# LacewingPXE_v3p1.net
KiCad netlist of a schematic drawn in Altium Designer
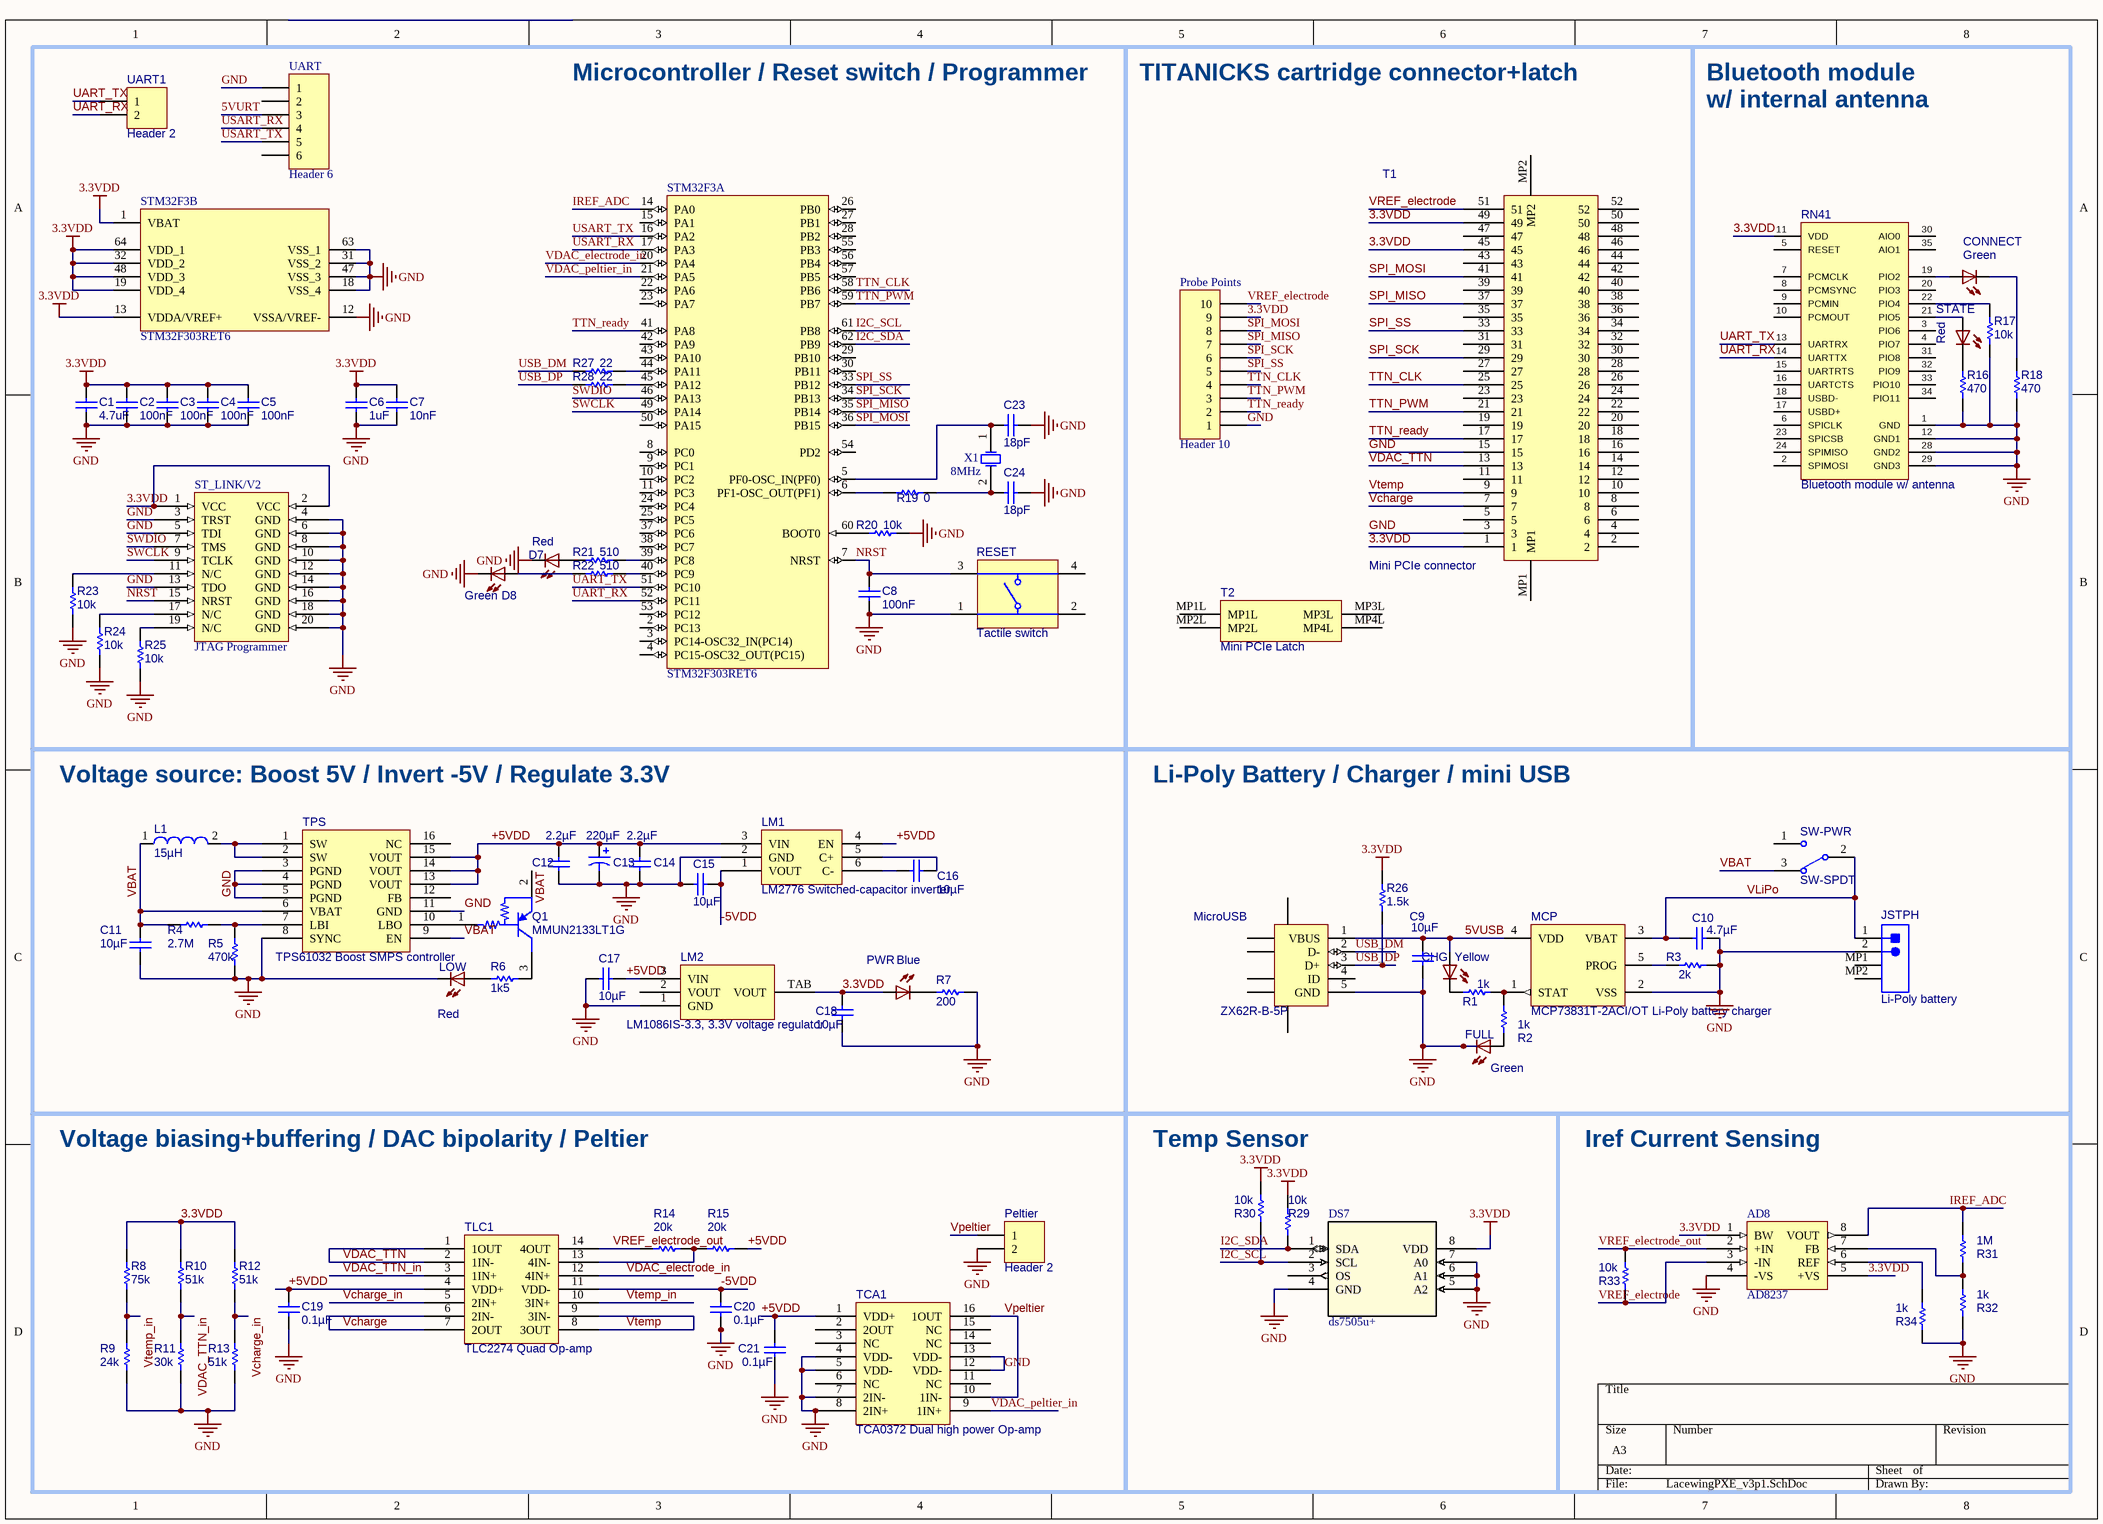
[diagram p0: LacewingPXE_v3p1.SchDoc]

(export (version "E")
  (design (tool "Eeschema 10.0.6"))
  (components
    (comp (ref "AD8")
      (value "AD8237")
      (footprint "ADI-RM-8_N")
      (libsource (lib "Device_mbd_v1") (part "AD8237"))
    )
    (comp (ref "C1")
      (value "4.7uF")
      (footprint "CAPC0603(1608)100_N")
      (description "Ceramic CAP0603 (1608 Metric) Thickness 1mm SMD")
      (libsource (lib "Altium Content Vault") (part "CAP"))
    )
    (comp (ref "C2")
      (value "100nF")
      (footprint "CAPC0603(1608)100_N")
      (description "Ceramic CAP0603 (1608 Metric) Thickness 1mm SMD")
      (libsource (lib "Altium Content Vault") (part "CAP"))
    )
    (comp (ref "C3")
      (value "100nF")
      (footprint "CAPC0603(1608)100_N")
      (description "Ceramic CAP0603 (1608 Metric) Thickness 1mm SMD")
      (libsource (lib "Altium Content Vault") (part "CAP"))
    )
    (comp (ref "C4")
      (value "100nF")
      (footprint "CAPC0603(1608)100_N")
      (description "Ceramic CAP0603 (1608 Metric) Thickness 1mm SMD")
      (libsource (lib "Altium Content Vault") (part "CAP"))
    )
    (comp (ref "C5")
      (value "100nF")
      (footprint "CAPC0603(1608)100_N")
      (description "Ceramic CAP0603 (1608 Metric) Thickness 1mm SMD")
      (libsource (lib "Altium Content Vault") (part "CAP"))
    )
    (comp (ref "C6")
      (value "1uF")
      (footprint "CAPC0603(1608)100_N")
      (description "Ceramic CAP0603 (1608 Metric) Thickness 1mm SMD")
      (libsource (lib "Altium Content Vault") (part "CAP"))
    )
    (comp (ref "C7")
      (value "10nF")
      (footprint "CAPC0603(1608)100_N")
      (description "Ceramic CAP0603 (1608 Metric) Thickness 1mm SMD")
      (libsource (lib "Altium Content Vault") (part "CAP"))
    )
    (comp (ref "C8")
      (value "100nF")
      (footprint "CAPC0603(1608)100_N")
      (description "Ceramic CAP0603 (1608 Metric) Thickness 1mm SMD")
      (libsource (lib "Altium Content Vault") (part "CAP"))
    )
    (comp (ref "C9")
      (value "10µF")
      (footprint "CAPC0805(2012)75_N")
      (description "Ceramic CAP0805 (2012 Metric) Thickness 0.75mm SMD")
      (libsource (lib "Altium Content Vault") (part "CMP-1036-00002-1"))
    )
    (comp (ref "C10")
      (value "4.7µF")
      (footprint "CAPC0603(1608)100_N")
      (description "Ceramic CAP0603 (1608 Metric) Thickness 1mm SMD")
      (libsource (lib "Altium Content Vault") (part "CAP"))
    )
    (comp (ref "C11")
      (value "10µF")
      (footprint "CAPC0805(2012)75_N")
      (description "Ceramic CAP0805 (2012 Metric) Thickness 0.75mm SMD")
      (libsource (lib "Altium Content Vault") (part "CMP-1036-00002-1"))
    )
    (comp (ref "C12")
      (value "2.2µF")
      (footprint "CAPC0805(2012)75_N")
      (description "Ceramic CAP0805 (2012 Metric) Thickness 0.75mm SMD")
      (libsource (lib "Altium Content Vault") (part "CMP-1036-00002-1"))
    )
    (comp (ref "C13")
      (value "220µF")
      (footprint "AVX-CAPC7343_V")
      (description "Capacitor, Tantalum, 220uF 10% 10V MCCT-D (7343-31)")
      (fields (field (name "PARTNUMBER") "TAJD227K010R") (field (name "MANUFACTURER") "AVX"))
      (libsource (lib "Altium Content Vault") (part "CMP-0279-00002-1"))
    )
    (comp (ref "C14")
      (value "2.2µF")
      (footprint "CAPC0805(2012)75_N")
      (description "Ceramic CAP0805 (2012 Metric) Thickness 0.75mm SMD")
      (libsource (lib "Altium Content Vault") (part "CMP-1036-00002-1"))
    )
    (comp (ref "C15")
      (value "10µF")
      (footprint "CAPC0805(2012)75_N")
      (description "Ceramic CAP0805 (2012 Metric) Thickness 0.75mm SMD")
      (libsource (lib "Altium Content Vault") (part "CMP-1036-00002-1"))
    )
    (comp (ref "C16")
      (value "10µF")
      (footprint "CAPC0805(2012)75_N")
      (description "Ceramic CAP0805 (2012 Metric) Thickness 0.75mm SMD")
      (libsource (lib "Altium Content Vault") (part "CMP-1036-00002-1"))
    )
    (comp (ref "C17")
      (value "10µF")
      (footprint "CAPC0805(2012)75_N")
      (description "Ceramic CAP0805 (2012 Metric) Thickness 0.75mm SMD")
      (libsource (lib "Altium Content Vault") (part "CMP-1036-00002-1"))
    )
    (comp (ref "C18")
      (value "10µF")
      (footprint "CAPC0805(2012)75_N")
      (description "Ceramic CAP0805 (2012 Metric) Thickness 0.75mm SMD")
      (libsource (lib "Altium Content Vault") (part "CMP-1036-00002-1"))
    )
    (comp (ref "C19")
      (value "0.1µF")
      (footprint "CAPC0603(1608)100_N")
      (description "Ceramic CAP0603 (1608 Metric) Thickness 1mm SMD")
      (libsource (lib "Device_mbd_v1") (part "CAP"))
    )
    (comp (ref "C20")
      (value "0.1µF")
      (footprint "CAPC0603(1608)100_N")
      (description "Ceramic CAP0603 (1608 Metric) Thickness 1mm SMD")
      (libsource (lib "Device_mbd_v1") (part "CAP"))
    )
    (comp (ref "C21")
      (value "0.1µF")
      (footprint "CAPC0603(1608)100_N")
      (description "Ceramic CAP0603 (1608 Metric) Thickness 1mm SMD")
      (libsource (lib "Device_mbd_v1") (part "CAP"))
    )
    (comp (ref "C23")
      (value "18pF")
      (footprint "CAPC0603(1608)100_N")
      (description "Ceramic CAP0603 (1608 Metric) Thickness 1mm SMD")
      (libsource (lib "Altium Content Vault") (part "CAP"))
    )
    (comp (ref "C24")
      (value "18pF")
      (footprint "CAPC0603(1608)100_N")
      (description "Ceramic CAP0603 (1608 Metric) Thickness 1mm SMD")
      (libsource (lib "Altium Content Vault") (part "CAP"))
    )
    (comp (ref "CHG")
      (value "Yellow")
      (footprint "LED-0603")
      (description "LED SMD 0603")
      (libsource (lib "TTN_chip") (part "LED0603"))
    )
    (comp (ref "CONNECT")
      (value "Green")
      (footprint "LED-0603")
      (description "LED SMD 0603")
      (libsource (lib "TTN_chip") (part "LED0603"))
    )
    (comp (ref "D7")
      (value "Red")
      (footprint "LED-0603")
      (description "LED SMD 0603")
      (libsource (lib "TTN_chip") (part "LED0603"))
    )
    (comp (ref "D8")
      (value "Green")
      (footprint "LED-0603")
      (description "LED SMD 0603")
      (libsource (lib "TTN_chip") (part "LED0603"))
    )
    (comp (ref "DS7")
      (value "ds7505u+")
      (footprint "21-0036K")
      (description "No Description Available")
      (fields (field (name "COPYRIGHT") "Copyright (C) 2018 Accelerated Designs. All rights reserved"))
      (libsource (lib "2019-05-15_15-51-07") (part "ds7505u+"))
    )
    (comp (ref "FULL")
      (value "Green")
      (footprint "LED-0603")
      (description "LED SMD 0603")
      (libsource (lib "TTN_chip") (part "LED0603"))
    )
    (comp (ref "JSTPH")
      (value "Li-Poly battery")
      (footprint "JST- S2B-PH-SM4-TB(LF)(SN)-2_V")
      (description "JST PH 2-pin 2-holder SMD")
      (libsource (lib "Altium Content Vault") (part "SYM-0368-00001-1"))
    )
    (comp (ref "L1")
      (value "15µH")
      (footprint "WE-PD 1050")
      (description "SMD-Shielded Power Inductor WE-PD 7447714150, L=15 µH")
      (libsource (lib "Altium Content Vault") (part "PAS-IND-INDUCTOR-2"))
    )
    (comp (ref "LM1")
      (value "LM2776 Switched-capacitor inverter")
      (footprint "TI-DBV6_M")
      (libsource (lib "Device_mbd_v1") (part "LM2776"))
    )
    (comp (ref "LM2")
      (value "LM1086IS-3.3, 3.3V voltage regulator")
      (footprint "TS3B_M")
      (libsource (lib "TTN_chip") (part "LM1086IS-3.3"))
    )
    (comp (ref "LOW")
      (value "Red")
      (footprint "LED-0603")
      (description "LED SMD 0603")
      (libsource (lib "TTN_chip") (part "LED0603"))
    )
    (comp (ref "MCP")
      (value "MCP73831T-2ACI/OT Li-Poly battery charger")
      (footprint "SOT-23-OT5_M")
      (libsource (lib "Altium Content Vault") (part "CMP-0133-00143-1"))
    )
    (comp (ref "MicroUSB")
      (value "ZX62R-B-5P")
      (footprint "HIRO-ZX62R-B-5P_V")
      (description "Connector; USBMicro-B,Reverse type, SMT; 5 Position; Right Angle")
      (libsource (lib "Altium Content Vault") (part "HIRO-ZX62R-B-5P-5"))
    )
    (comp (ref "Peltier")
      (value "Header 2")
      (footprint "HDR1X2")
      (description "Header, 2-Pin")
      (fields (field (name "PUBLISHER") "Altium Limited"))
      (libsource (lib "Miscellaneous Connectors") (part "Header 2"))
    )
    (comp (ref "Probe Points")
      (value "Header 10")
      (footprint "HDR1X10")
      (description "Header, 10-Pin")
      (fields (field (name "PUBLISHER") "Altium Limited"))
      (libsource (lib "Miscellaneous Connectors") (part "Header 10"))
    )
    (comp (ref "PWR")
      (value "Blue")
      (footprint "LED-0603")
      (description "LED SMD 0603")
      (libsource (lib "TTN_chip") (part "LED0603"))
    )
    (comp (ref "Q1")
      (value "MMUN2133LT1G")
      (footprint "ONSC-SOT-23-3-318-08_V")
      (libsource (lib "Altium Content Vault") (part "CMP-0630-00284-1"))
    )
    (comp (ref "R1")
      (value "1k")
      (footprint "RESC0603(1608)_N")
      (description "RES0603 (1608 Metric)  SMD")
      (libsource (lib "Altium Content Vault") (part "RES"))
    )
    (comp (ref "R2")
      (value "1k")
      (footprint "RESC0603(1608)_N")
      (description "RES0603 (1608 Metric)  SMD")
      (libsource (lib "Altium Content Vault") (part "RES"))
    )
    (comp (ref "R3")
      (value "2k")
      (footprint "RESC0603(1608)_N")
      (description "RES0603 (1608 Metric)  SMD")
      (libsource (lib "Altium Content Vault") (part "RES"))
    )
    (comp (ref "R4")
      (value "2.7M")
      (footprint "RESC0603(1608)_N")
      (description "RES0603 (1608 Metric)  SMD")
      (libsource (lib "Altium Content Vault") (part "RES"))
    )
    (comp (ref "R5")
      (value "470k")
      (footprint "RESC0603(1608)_N")
      (description "RES0603 (1608 Metric)  SMD")
      (libsource (lib "Altium Content Vault") (part "RES"))
    )
    (comp (ref "R6")
      (value "1k5")
      (footprint "RESC0603(1608)_N")
      (description "RES0603 (1608 Metric)  SMD")
      (libsource (lib "Altium Content Vault") (part "RES"))
    )
    (comp (ref "R7")
      (value "200")
      (footprint "RESC0603(1608)_N")
      (description "RES0603 (1608 Metric)  SMD")
      (libsource (lib "Altium Content Vault") (part "RES"))
    )
    (comp (ref "R8")
      (value "75k")
      (footprint "RESC0603(1608)_N")
      (description "RES0603 (1608 Metric)  SMD")
      (libsource (lib "Altium Content Vault") (part "RES"))
    )
    (comp (ref "R9")
      (value "24k")
      (footprint "RESC0603(1608)_N")
      (description "RES0603 (1608 Metric)  SMD")
      (libsource (lib "Altium Content Vault") (part "RES"))
    )
    (comp (ref "R10")
      (value "51k")
      (footprint "RESC0603(1608)_N")
      (description "RES0603 (1608 Metric)  SMD")
      (libsource (lib "Altium Content Vault") (part "RES"))
    )
    (comp (ref "R11")
      (value "30k")
      (footprint "RESC0603(1608)_N")
      (description "RES0603 (1608 Metric)  SMD")
      (libsource (lib "Altium Content Vault") (part "RES"))
    )
    (comp (ref "R12")
      (value "51k")
      (footprint "RESC0603(1608)_N")
      (description "RES0603 (1608 Metric)  SMD")
      (libsource (lib "Altium Content Vault") (part "RES"))
    )
    (comp (ref "R13")
      (value "51k")
      (footprint "RESC0603(1608)_N")
      (description "RES0603 (1608 Metric)  SMD")
      (libsource (lib "Altium Content Vault") (part "RES"))
    )
    (comp (ref "R14")
      (value "20k")
      (footprint "RESC0603(1608)_N")
      (description "RES0603 (1608 Metric)  SMD")
      (libsource (lib "Altium Content Vault") (part "RES"))
    )
    (comp (ref "R15")
      (value "20k")
      (footprint "RESC0603(1608)_N")
      (description "RES0603 (1608 Metric)  SMD")
      (libsource (lib "Altium Content Vault") (part "RES"))
    )
    (comp (ref "R16")
      (value "470")
      (footprint "RESC0603(1608)_N")
      (description "RES0603 (1608 Metric)  SMD")
      (libsource (lib "Altium Content Vault") (part "RES"))
    )
    (comp (ref "R17")
      (value "10k")
      (footprint "RESC0603(1608)_N")
      (description "RES0603 (1608 Metric)  SMD")
      (libsource (lib "Altium Content Vault") (part "RES"))
    )
    (comp (ref "R18")
      (value "470")
      (footprint "RESC0603(1608)_N")
      (description "RES0603 (1608 Metric)  SMD")
      (libsource (lib "Altium Content Vault") (part "RES"))
    )
    (comp (ref "R19")
      (value "0")
      (footprint "RESC0603(1608)_N")
      (description "RES0603 (1608 Metric)  SMD")
      (libsource (lib "Altium Content Vault") (part "RES"))
    )
    (comp (ref "R20")
      (value "10k")
      (footprint "RESC0603(1608)_N")
      (description "RES0603 (1608 Metric)  SMD")
      (libsource (lib "Altium Content Vault") (part "RES"))
    )
    (comp (ref "R21")
      (value "510")
      (footprint "RESC0603(1608)_N")
      (description "RES0603 (1608 Metric)  SMD")
      (libsource (lib "Altium Content Vault") (part "RES"))
    )
    (comp (ref "R22")
      (value "510")
      (footprint "RESC0603(1608)_N")
      (description "RES0603 (1608 Metric)  SMD")
      (libsource (lib "Altium Content Vault") (part "RES"))
    )
    (comp (ref "R23")
      (value "10k")
      (footprint "RESC0603(1608)_N")
      (description "RES0603 (1608 Metric)  SMD")
      (libsource (lib "Altium Content Vault") (part "RES"))
    )
    (comp (ref "R24")
      (value "10k")
      (footprint "RESC0603(1608)_N")
      (description "RES0603 (1608 Metric)  SMD")
      (libsource (lib "Altium Content Vault") (part "RES"))
    )
    (comp (ref "R25")
      (value "10k")
      (footprint "RESC0603(1608)_N")
      (description "RES0603 (1608 Metric)  SMD")
      (libsource (lib "Altium Content Vault") (part "RES"))
    )
    (comp (ref "R26")
      (value "1.5k")
      (footprint "RESC0603(1608)_N")
      (description "RES0603 (1608 Metric)  SMD")
      (libsource (lib "Altium Content Vault") (part "RES"))
    )
    (comp (ref "R27")
      (value "22")
      (footprint "RESC0603(1608)_N")
      (description "RES0603 (1608 Metric)  SMD")
      (libsource (lib "Altium Content Vault") (part "RES"))
    )
    (comp (ref "R28")
      (value "22")
      (footprint "RESC0603(1608)_N")
      (description "RES0603 (1608 Metric)  SMD")
      (libsource (lib "Altium Content Vault") (part "RES"))
    )
    (comp (ref "R29")
      (value "10k")
      (footprint "RESC0603(1608)_N")
      (description "RES0603 (1608 Metric)  SMD")
      (libsource (lib "Altium Content Vault") (part "RES"))
    )
    (comp (ref "R30")
      (value "10k")
      (footprint "RESC0603(1608)_N")
      (description "RES0603 (1608 Metric)  SMD")
      (libsource (lib "Altium Content Vault") (part "RES"))
    )
    (comp (ref "R31")
      (value "1M")
      (footprint "RESC0603(1608)_N")
      (description "RES0603 (1608 Metric)  SMD")
      (libsource (lib "Altium Content Vault") (part "RES"))
    )
    (comp (ref "R32")
      (value "1k")
      (footprint "RESC0603(1608)_N")
      (description "RES0603 (1608 Metric)  SMD")
      (libsource (lib "Altium Content Vault") (part "RES"))
    )
    (comp (ref "R33")
      (value "10k")
      (footprint "RESC0603(1608)_N")
      (description "RES0603 (1608 Metric)  SMD")
      (libsource (lib "Altium Content Vault") (part "RES"))
    )
    (comp (ref "R34")
      (value "1k")
      (footprint "RESC0603(1608)_N")
      (description "RES0603 (1608 Metric)  SMD")
      (libsource (lib "Altium Content Vault") (part "RES"))
    )
    (comp (ref "RESET")
      (value "Tactile switch")
      (footprint "OMRON-B3F-1000-4_V")
      (description "ORMON B3F-10XX")
      (libsource (lib "TTN_chip") (part "SW-SPST-4_A"))
    )
    (comp (ref "RN41")
      (value "Bluetooth module w/ antenna")
      (footprint "RN41")
      (description "Bluetooth SMD module")
      (libsource (lib "Device_mbd_v1") (part "BLUETOOTH-RN41"))
    )
    (comp (ref "STATE")
      (value "Red")
      (footprint "LED-0603")
      (description "LED SMD 0603")
      (libsource (lib "TTN_chip") (part "LED0603"))
    )
    (comp (ref "STM32F3")
      (value "STM32F303RET6")
      (footprint "STM-LQFP64_V")
      (fields (field (name "PARTNUMBER") "STM32F303RBT6"))
      (libsource (lib "STMicroelectronics STM32 F3 new") (part "STM32F303RBT6_1"))
    )
    (comp (ref "ST_LINK/V2")
      (value "JTAG Programmer")
      (footprint "JTAG2")
      (libsource (lib "Device_mbd_v1") (part "JTAG"))
    )
    (comp (ref "SW-PWR")
      (value "SW-SPDT")
      (footprint "SWITCH SPDT CS12ANW03")
      (description "Switch SPDT CS12ANW03")
      (libsource (lib "TTN_chip") (part "SW-SPDT"))
    )
    (comp (ref "T1")
      (value "Mini PCIe connector")
      (footprint "Molex Conn-67910")
      (libsource (lib "Device_mbd_v1") (part "Mini PCIe connector"))
    )
    (comp (ref "T2")
      (value "Mini PCIe Latch")
      (footprint "Molex Latch-48099")
      (libsource (lib "Device_mbd_v1") (part "Mini PCIe Latch"))
    )
    (comp (ref "TCA1")
      (value "TCA0372 Dual high power Op-amp")
      (footprint "ONSC-SOIC-16-751G-03_V")
      (libsource (lib "TTN_chip") (part "TCA0372"))
    )
    (comp (ref "TLC1")
      (value "TLC2274 Quad Op-amp")
      (footprint "TI-D14_M")
      (libsource (lib "TTN_chip") (part "TLC2274"))
    )
    (comp (ref "TPS")
      (value "TPS61032 Boost SMPS controller")
      (footprint "PW0016A_M")
      (libsource (lib "TTN_chip") (part "TPS61032"))
    )
    (comp (ref "UART")
      (value "Header 6")
      (footprint "HDR1X6")
      (description "Header, 6-Pin")
      (fields (field (name "PUBLISHER") "Altium Limited"))
      (libsource (lib "Miscellaneous Connectors") (part "Header 6"))
    )
    (comp (ref "UART1")
      (value "Header 2")
      (footprint "HDR1X2")
      (description "Header, 2-Pin")
      (fields (field (name "PUBLISHER") "Altium Limited"))
      (libsource (lib "Miscellaneous Connectors") (part "Header 2"))
    )
    (comp (ref "X1")
      (value "8MHz")
      (footprint "QCL")
      (description "Crystal Oscillator")
      (fields (field (name "PUBLISHER") "Altium Limited"))
      (libsource (lib "Miscellaneous Devices") (part "XTAL"))
    )
  )
  (nets
    (net (code "1") (name "/+5VDD") (class "Default")
      (node (ref "C12") (pin "2") (pinfunction "2_2") (pintype "passive"))
      (node (ref "C13") (pin "1") (pinfunction "1_1") (pintype "passive"))
      (node (ref "C14") (pin "2") (pinfunction "2_2") (pintype "passive"))
      (node (ref "C17") (pin "1") (pinfunction "1_1") (pintype "passive"))
      (node (ref "C19") (pin "2") (pinfunction "2_2") (pintype "passive"))
      (node (ref "C21") (pin "2") (pinfunction "2_2") (pintype "passive"))
      (node (ref "LM1") (pin "3") (pinfunction "VIN_3") (pintype "passive"))
      (node (ref "LM1") (pin "4") (pinfunction "EN_4") (pintype "passive"))
      (node (ref "LM2") (pin "3") (pinfunction "VIN_3") (pintype "passive"))
      (node (ref "R15") (pin "2") (pinfunction "2_2") (pintype "passive"))
      (node (ref "TCA1") (pin "1") (pinfunction "VDD+_1") (pintype "passive"))
      (node (ref "TLC1") (pin "4") (pinfunction "VDD+_4") (pintype "passive"))
      (node (ref "TPS") (pin "13") (pinfunction "VOUT_13") (pintype "passive"))
      (node (ref "TPS") (pin "14") (pinfunction "VOUT_14") (pintype "passive"))
      (node (ref "TPS") (pin "15") (pinfunction "VOUT_15") (pintype "passive"))
    )
    (net (code "2") (name "/-5VDD") (class "Default")
      (node (ref "C15") (pin "1") (pinfunction "1_1") (pintype "passive"))
      (node (ref "C20") (pin "2") (pinfunction "2_2") (pintype "passive"))
      (node (ref "LM1") (pin "1") (pinfunction "VOUT_1") (pintype "passive"))
      (node (ref "TLC1") (pin "11") (pinfunction "VDD-_11") (pintype "passive"))
    )
    (net (code "3") (name "/5VURT") (class "Default")
      (node (ref "UART") (pin "3") (pinfunction "3_3") (pintype "passive"))
    )
    (net (code "4") (name "/5VUSB") (class "Default")
      (node (ref "C9") (pin "2") (pinfunction "2_2") (pintype "passive"))
      (node (ref "CHG") (pin "A") (pinfunction "A_A") (pintype "passive"))
      (node (ref "MCP") (pin "4") (pinfunction "VDD_4") (pintype "power_in"))
      (node (ref "MicroUSB") (pin "1") (pinfunction "VBUS_1") (pintype "power_in"))
    )
    (net (code "5") (name "/I2C_SCL") (class "Default")
      (node (ref "DS7") (pin "2") (pinfunction "SCL_2") (pintype "input"))
      (node (ref "R30") (pin "1") (pinfunction "1_1") (pintype "passive"))
      (node (ref "STM32F3") (pin "61") (pinfunction "PB8_61") (pintype "bidirectional"))
    )
    (net (code "6") (name "/I2C_SDA") (class "Default")
      (node (ref "DS7") (pin "1") (pinfunction "SDA_1") (pintype "bidirectional"))
      (node (ref "R29") (pin "1") (pinfunction "1_1") (pintype "passive"))
      (node (ref "STM32F3") (pin "62") (pinfunction "PB9_62") (pintype "bidirectional"))
    )
    (net (code "7") (name "/IREF_ADC") (class "Default")
      (node (ref "AD8") (pin "8") (pinfunction "VOUT_8") (pintype "output"))
      (node (ref "R31") (pin "2") (pinfunction "2_2") (pintype "passive"))
      (node (ref "STM32F3") (pin "14") (pinfunction "PA0_14") (pintype "bidirectional"))
    )
    (net (code "8") (name "/NRST") (class "Default")
      (node (ref "C8") (pin "1") (pinfunction "1_1") (pintype "passive"))
      (node (ref "RESET") (pin "3") (pinfunction "3_3") (pintype "passive"))
      (node (ref "STM32F3") (pin "7") (pinfunction "NRST_7") (pintype "bidirectional"))
      (node (ref "ST_LINK/V2") (pin "15") (pinfunction "NRST_15") (pintype "input"))
    )
    (net (code "9") (name "/SPI_MISO") (class "Default")
      (node (ref "Probe Points") (pin "7") (pinfunction "7_7") (pintype "passive"))
      (node (ref "STM32F3") (pin "35") (pinfunction "PB14_35") (pintype "bidirectional"))
      (node (ref "T1") (pin "37") (pinfunction "37_37") (pintype "passive"))
    )
    (net (code "10") (name "/SPI_MOSI") (class "Default")
      (node (ref "Probe Points") (pin "8") (pinfunction "8_8") (pintype "passive"))
      (node (ref "STM32F3") (pin "36") (pinfunction "PB15_36") (pintype "bidirectional"))
      (node (ref "T1") (pin "41") (pinfunction "41_41") (pintype "passive"))
    )
    (net (code "11") (name "/SPI_SCK") (class "Default")
      (node (ref "Probe Points") (pin "6") (pinfunction "6_6") (pintype "passive"))
      (node (ref "STM32F3") (pin "34") (pinfunction "PB13_34") (pintype "bidirectional"))
      (node (ref "T1") (pin "29") (pinfunction "29_29") (pintype "passive"))
    )
    (net (code "12") (name "/SPI_SS") (class "Default")
      (node (ref "Probe Points") (pin "5") (pinfunction "5_5") (pintype "passive"))
      (node (ref "STM32F3") (pin "33") (pinfunction "PB12_33") (pintype "bidirectional"))
      (node (ref "T1") (pin "33") (pinfunction "33_33") (pintype "passive"))
    )
    (net (code "13") (name "/SWCLK") (class "Default")
      (node (ref "STM32F3") (pin "49") (pinfunction "PA14_49") (pintype "bidirectional"))
      (node (ref "ST_LINK/V2") (pin "9") (pinfunction "TCLK_9") (pintype "input"))
    )
    (net (code "14") (name "/SWDIO") (class "Default")
      (node (ref "STM32F3") (pin "46") (pinfunction "PA13_46") (pintype "bidirectional"))
      (node (ref "ST_LINK/V2") (pin "7") (pinfunction "TMS_7") (pintype "input"))
    )
    (net (code "15") (name "/TTN_CLK") (class "Default")
      (node (ref "Probe Points") (pin "4") (pinfunction "4_4") (pintype "passive"))
      (node (ref "STM32F3") (pin "58") (pinfunction "PB6_58") (pintype "bidirectional"))
      (node (ref "T1") (pin "25") (pinfunction "25_25") (pintype "passive"))
    )
    (net (code "16") (name "/TTN_PWM") (class "Default")
      (node (ref "Probe Points") (pin "3") (pinfunction "3_3") (pintype "passive"))
      (node (ref "STM32F3") (pin "59") (pinfunction "PB7_59") (pintype "bidirectional"))
      (node (ref "T1") (pin "21") (pinfunction "21_21") (pintype "passive"))
    )
    (net (code "17") (name "/TTN_ready") (class "Default")
      (node (ref "Probe Points") (pin "2") (pinfunction "2_2") (pintype "passive"))
      (node (ref "STM32F3") (pin "41") (pinfunction "PA8_41") (pintype "bidirectional"))
      (node (ref "T1") (pin "17") (pinfunction "17_17") (pintype "passive"))
    )
    (net (code "18") (name "/UART_RX") (class "Default")
      (node (ref "RN41") (pin "14") (pinfunction "UARTTX_14") (pintype "passive"))
      (node (ref "STM32F3") (pin "52") (pinfunction "PC11_52") (pintype "bidirectional"))
      (node (ref "UART1") (pin "2") (pinfunction "2_2") (pintype "passive"))
    )
    (net (code "19") (name "/UART_TX") (class "Default")
      (node (ref "RN41") (pin "13") (pinfunction "UARTRX_13") (pintype "passive"))
      (node (ref "STM32F3") (pin "51") (pinfunction "PC10_51") (pintype "bidirectional"))
      (node (ref "UART1") (pin "1") (pinfunction "1_1") (pintype "passive"))
    )
    (net (code "20") (name "/USART_RX") (class "Default")
      (node (ref "STM32F3") (pin "17") (pinfunction "PA3_17") (pintype "bidirectional"))
      (node (ref "UART") (pin "4") (pinfunction "4_4") (pintype "passive"))
    )
    (net (code "21") (name "/USART_TX") (class "Default")
      (node (ref "STM32F3") (pin "16") (pinfunction "PA2_16") (pintype "bidirectional"))
      (node (ref "UART") (pin "5") (pinfunction "5_5") (pintype "passive"))
    )
    (net (code "22") (name "/USB_DM") (class "Default")
      (node (ref "MicroUSB") (pin "2") (pinfunction "D-_2") (pintype "bidirectional"))
      (node (ref "R27") (pin "1") (pinfunction "1_1") (pintype "passive"))
    )
    (net (code "23") (name "/USB_DP") (class "Default")
      (node (ref "MicroUSB") (pin "3") (pinfunction "D+_3") (pintype "bidirectional"))
      (node (ref "R26") (pin "1") (pinfunction "1_1") (pintype "passive"))
      (node (ref "R28") (pin "1") (pinfunction "1_1") (pintype "passive"))
    )
    (net (code "24") (name "/VBAT") (class "Default")
      (node (ref "C11") (pin "2") (pinfunction "2_2") (pintype "passive"))
      (node (ref "L1") (pin "1") (pinfunction "1_1") (pintype "passive"))
      (node (ref "Q1") (pin "2") (pinfunction "E_2") (pintype "passive"))
      (node (ref "R4") (pin "2") (pinfunction "2_2") (pintype "passive"))
      (node (ref "SW-PWR") (pin "3") (pinfunction "3_3") (pintype "passive"))
      (node (ref "TPS") (pin "6") (pinfunction "VBAT_6") (pintype "passive"))
      (node (ref "TPS") (pin "9") (pinfunction "EN_9") (pintype "passive"))
    )
    (net (code "25") (name "/VDAC_TTN") (class "Default")
      (node (ref "T1") (pin "13") (pinfunction "13_13") (pintype "passive"))
      (node (ref "TLC1") (pin "1") (pinfunction "1OUT_1") (pintype "passive"))
      (node (ref "TLC1") (pin "2") (pinfunction "1IN-_2") (pintype "passive"))
    )
    (net (code "26") (name "/VDAC_TTN_in") (class "Default")
      (node (ref "R10") (pin "2") (pinfunction "2_2") (pintype "passive"))
      (node (ref "R11") (pin "1") (pinfunction "1_1") (pintype "passive"))
      (node (ref "TLC1") (pin "3") (pinfunction "1IN+_3") (pintype "passive"))
    )
    (net (code "27") (name "/VDAC_electrode_in") (class "Default")
      (node (ref "STM32F3") (pin "20") (pinfunction "PA4_20") (pintype "bidirectional"))
      (node (ref "TLC1") (pin "12") (pinfunction "4IN+_12") (pintype "passive"))
    )
    (net (code "28") (name "/VDAC_peltier_in") (class "Default")
      (node (ref "STM32F3") (pin "21") (pinfunction "PA5_21") (pintype "bidirectional"))
      (node (ref "TCA1") (pin "9") (pinfunction "1IN+_9") (pintype "passive"))
    )
    (net (code "29") (name "/VLiPo") (class "Default")
      (node (ref "C10") (pin "2") (pinfunction "2_2") (pintype "passive"))
      (node (ref "JSTPH") (pin "1") (pinfunction "1_1") (pintype "passive"))
      (node (ref "MCP") (pin "3") (pinfunction "VBAT_3") (pintype "power_in"))
      (node (ref "SW-PWR") (pin "2") (pinfunction "2_2") (pintype "passive"))
    )
    (net (code "30") (name "/VREF_electrode") (class "Default")
      (node (ref "AD8") (pin "3") (pinfunction "-IN_3") (pintype "input"))
      (node (ref "Probe Points") (pin "10") (pinfunction "10_10") (pintype "passive"))
      (node (ref "R33") (pin "1") (pinfunction "1_1") (pintype "passive"))
      (node (ref "T1") (pin "51") (pinfunction "51_51") (pintype "passive"))
    )
    (net (code "31") (name "/VREF_electrode_out") (class "Default")
      (node (ref "AD8") (pin "2") (pinfunction "+IN_2") (pintype "input"))
      (node (ref "R14") (pin "1") (pinfunction "1_1") (pintype "passive"))
      (node (ref "R33") (pin "2") (pinfunction "2_2") (pintype "passive"))
      (node (ref "TLC1") (pin "14") (pinfunction "4OUT_14") (pintype "passive"))
    )
    (net (code "32") (name "/Vcharge") (class "Default")
      (node (ref "T1") (pin "7") (pinfunction "7_7") (pintype "passive"))
      (node (ref "TLC1") (pin "6") (pinfunction "2IN-_6") (pintype "passive"))
      (node (ref "TLC1") (pin "7") (pinfunction "2OUT_7") (pintype "passive"))
    )
    (net (code "33") (name "/Vcharge_in") (class "Default")
      (node (ref "R12") (pin "2") (pinfunction "2_2") (pintype "passive"))
      (node (ref "R13") (pin "1") (pinfunction "1_1") (pintype "passive"))
      (node (ref "TLC1") (pin "5") (pinfunction "2IN+_5") (pintype "passive"))
    )
    (net (code "34") (name "/Vpeltier") (class "Default")
      (node (ref "Peltier") (pin "1") (pinfunction "1_1") (pintype "passive"))
      (node (ref "TCA1") (pin "10") (pinfunction "1IN-_10") (pintype "passive"))
      (node (ref "TCA1") (pin "16") (pinfunction "1OUT_16") (pintype "passive"))
    )
    (net (code "35") (name "/Vtemp") (class "Default")
      (node (ref "T1") (pin "9") (pinfunction "9_9") (pintype "passive"))
      (node (ref "TLC1") (pin "8") (pinfunction "3OUT_8") (pintype "passive"))
      (node (ref "TLC1") (pin "9") (pinfunction "3IN-_9") (pintype "passive"))
    )
    (net (code "36") (name "/Vtemp_in") (class "Default")
      (node (ref "R8") (pin "2") (pinfunction "2_2") (pintype "passive"))
      (node (ref "R9") (pin "1") (pinfunction "1_1") (pintype "passive"))
      (node (ref "TLC1") (pin "10") (pinfunction "3IN+_10") (pintype "passive"))
    )
    (net (code "37") (name "3.3VDD") (class "Default")
      (node (ref "AD8") (pin "1") (pinfunction "BW_1") (pintype "input"))
      (node (ref "AD8") (pin "5") (pinfunction "+VS_5") (pintype "power_in"))
      (node (ref "C1") (pin "1") (pinfunction "1_1") (pintype "passive"))
      (node (ref "C18") (pin "2") (pinfunction "2_2") (pintype "passive"))
      (node (ref "C2") (pin "1") (pinfunction "1_1") (pintype "passive"))
      (node (ref "C3") (pin "1") (pinfunction "1_1") (pintype "passive"))
      (node (ref "C4") (pin "1") (pinfunction "1_1") (pintype "passive"))
      (node (ref "C5") (pin "1") (pinfunction "1_1") (pintype "passive"))
      (node (ref "C6") (pin "1") (pinfunction "1_1") (pintype "passive"))
      (node (ref "C7") (pin "1") (pinfunction "1_1") (pintype "passive"))
      (node (ref "DS7") (pin "8") (pinfunction "VDD_8") (pintype "power_in"))
      (node (ref "LM2") (pin "TAB") (pinfunction "VOUT_TAB") (pintype "passive"))
      (node (ref "PWR") (pin "A") (pinfunction "A_A") (pintype "passive"))
      (node (ref "Probe Points") (pin "9") (pinfunction "9_9") (pintype "passive"))
      (node (ref "R10") (pin "1") (pinfunction "1_1") (pintype "passive"))
      (node (ref "R12") (pin "1") (pinfunction "1_1") (pintype "passive"))
      (node (ref "R26") (pin "2") (pinfunction "2_2") (pintype "passive"))
      (node (ref "R29") (pin "2") (pinfunction "2_2") (pintype "passive"))
      (node (ref "R30") (pin "2") (pinfunction "2_2") (pintype "passive"))
      (node (ref "R8") (pin "1") (pinfunction "1_1") (pintype "passive"))
      (node (ref "RN41") (pin "11") (pinfunction "VDD_11") (pintype "passive"))
      (node (ref "STM32F3") (pin "1") (pinfunction "VBAT_1") (pintype "power_in"))
      (node (ref "STM32F3") (pin "13") (pinfunction "VDDA/VREF+_13") (pintype "power_in"))
      (node (ref "STM32F3") (pin "19") (pinfunction "VDD_4_19") (pintype "power_in"))
      (node (ref "STM32F3") (pin "32") (pinfunction "VDD_2_32") (pintype "power_in"))
      (node (ref "STM32F3") (pin "48") (pinfunction "VDD_3_48") (pintype "power_in"))
      (node (ref "STM32F3") (pin "64") (pinfunction "VDD_1_64") (pintype "power_in"))
      (node (ref "ST_LINK/V2") (pin "1") (pinfunction "VCC_1") (pintype "input"))
      (node (ref "ST_LINK/V2") (pin "2") (pinfunction "VCC_2") (pintype "input"))
      (node (ref "T1") (pin "1") (pinfunction "1_1") (pintype "passive"))
      (node (ref "T1") (pin "45") (pinfunction "45_45") (pintype "passive"))
      (node (ref "T1") (pin "49") (pinfunction "49_49") (pintype "passive"))
    )
    (net (code "38") (name "GND") (class "Default")
      (node (ref "AD8") (pin "4") (pinfunction "-VS_4") (pintype "power_in"))
      (node (ref "C1") (pin "2") (pinfunction "2_2") (pintype "passive"))
      (node (ref "C10") (pin "1") (pinfunction "1_1") (pintype "passive"))
      (node (ref "C11") (pin "1") (pinfunction "1_1") (pintype "passive"))
      (node (ref "C12") (pin "1") (pinfunction "1_1") (pintype "passive"))
      (node (ref "C13") (pin "2") (pinfunction "2_2") (pintype "passive"))
      (node (ref "C14") (pin "1") (pinfunction "1_1") (pintype "passive"))
      (node (ref "C15") (pin "2") (pinfunction "2_2") (pintype "passive"))
      (node (ref "C17") (pin "2") (pinfunction "2_2") (pintype "passive"))
      (node (ref "C18") (pin "1") (pinfunction "1_1") (pintype "passive"))
      (node (ref "C19") (pin "1") (pinfunction "1_1") (pintype "passive"))
      (node (ref "C2") (pin "2") (pinfunction "2_2") (pintype "passive"))
      (node (ref "C20") (pin "1") (pinfunction "1_1") (pintype "passive"))
      (node (ref "C21") (pin "1") (pinfunction "1_1") (pintype "passive"))
      (node (ref "C23") (pin "2") (pinfunction "2_2") (pintype "passive"))
      (node (ref "C24") (pin "2") (pinfunction "2_2") (pintype "passive"))
      (node (ref "C3") (pin "2") (pinfunction "2_2") (pintype "passive"))
      (node (ref "C4") (pin "2") (pinfunction "2_2") (pintype "passive"))
      (node (ref "C5") (pin "2") (pinfunction "2_2") (pintype "passive"))
      (node (ref "C6") (pin "2") (pinfunction "2_2") (pintype "passive"))
      (node (ref "C7") (pin "2") (pinfunction "2_2") (pintype "passive"))
      (node (ref "C8") (pin "2") (pinfunction "2_2") (pintype "passive"))
      (node (ref "C9") (pin "1") (pinfunction "1_1") (pintype "passive"))
      (node (ref "D7") (pin "C") (pinfunction "C_C") (pintype "passive"))
      (node (ref "D8") (pin "C") (pinfunction "C_C") (pintype "passive"))
      (node (ref "DS7") (pin "4") (pinfunction "GND_4") (pintype "power_in"))
      (node (ref "DS7") (pin "5") (pinfunction "A2_5") (pintype "input"))
      (node (ref "DS7") (pin "6") (pinfunction "A1_6") (pintype "input"))
      (node (ref "DS7") (pin "7") (pinfunction "A0_7") (pintype "input"))
      (node (ref "FULL") (pin "C") (pinfunction "C_C") (pintype "passive"))
      (node (ref "JSTPH") (pin "2") (pinfunction "2_2") (pintype "passive"))
      (node (ref "LM1") (pin "2") (pinfunction "GND_2") (pintype "passive"))
      (node (ref "LM2") (pin "1") (pinfunction "GND_1") (pintype "passive"))
      (node (ref "LOW") (pin "C") (pinfunction "C_C") (pintype "passive"))
      (node (ref "MCP") (pin "2") (pinfunction "VSS_2") (pintype "power_in"))
      (node (ref "MicroUSB") (pin "5") (pinfunction "GND_5") (pintype "power_in"))
      (node (ref "Peltier") (pin "2") (pinfunction "2_2") (pintype "passive"))
      (node (ref "Probe Points") (pin "1") (pinfunction "1_1") (pintype "passive"))
      (node (ref "R11") (pin "2") (pinfunction "2_2") (pintype "passive"))
      (node (ref "R13") (pin "2") (pinfunction "2_2") (pintype "passive"))
      (node (ref "R16") (pin "1") (pinfunction "1_1") (pintype "passive"))
      (node (ref "R17") (pin "1") (pinfunction "1_1") (pintype "passive"))
      (node (ref "R18") (pin "1") (pinfunction "1_1") (pintype "passive"))
      (node (ref "R20") (pin "2") (pinfunction "2_2") (pintype "passive"))
      (node (ref "R23") (pin "1") (pinfunction "1_1") (pintype "passive"))
      (node (ref "R24") (pin "1") (pinfunction "1_1") (pintype "passive"))
      (node (ref "R25") (pin "1") (pinfunction "1_1") (pintype "passive"))
      (node (ref "R3") (pin "2") (pinfunction "2_2") (pintype "passive"))
      (node (ref "R32") (pin "1") (pinfunction "1_1") (pintype "passive"))
      (node (ref "R34") (pin "1") (pinfunction "1_1") (pintype "passive"))
      (node (ref "R5") (pin "2") (pinfunction "2_2") (pintype "passive"))
      (node (ref "R7") (pin "2") (pinfunction "2_2") (pintype "passive"))
      (node (ref "R9") (pin "2") (pinfunction "2_2") (pintype "passive"))
      (node (ref "RESET") (pin "1") (pinfunction "1_1") (pintype "passive"))
      (node (ref "RN41") (pin "1") (pinfunction "GND_1") (pintype "passive"))
      (node (ref "RN41") (pin "12") (pinfunction "GND1_12") (pintype "passive"))
      (node (ref "RN41") (pin "28") (pinfunction "GND2_28") (pintype "passive"))
      (node (ref "RN41") (pin "29") (pinfunction "GND3_29") (pintype "passive"))
      (node (ref "STM32F3") (pin "12") (pinfunction "VSSA/VREF-_12") (pintype "power_in"))
      (node (ref "STM32F3") (pin "18") (pinfunction "VSS_4_18") (pintype "power_in"))
      (node (ref "STM32F3") (pin "31") (pinfunction "VSS_2_31") (pintype "power_in"))
      (node (ref "STM32F3") (pin "47") (pinfunction "VSS_3_47") (pintype "power_in"))
      (node (ref "STM32F3") (pin "63") (pinfunction "VSS_1_63") (pintype "power_in"))
      (node (ref "ST_LINK/V2") (pin "10") (pinfunction "GND_10") (pintype "input"))
      (node (ref "ST_LINK/V2") (pin "12") (pinfunction "GND_12") (pintype "input"))
      (node (ref "ST_LINK/V2") (pin "13") (pinfunction "TDO_13") (pintype "input"))
      (node (ref "ST_LINK/V2") (pin "14") (pinfunction "GND_14") (pintype "input"))
      (node (ref "ST_LINK/V2") (pin "16") (pinfunction "GND_16") (pintype "input"))
      (node (ref "ST_LINK/V2") (pin "18") (pinfunction "GND_18") (pintype "input"))
      (node (ref "ST_LINK/V2") (pin "20") (pinfunction "GND_20") (pintype "input"))
      (node (ref "ST_LINK/V2") (pin "3") (pinfunction "TRST_3") (pintype "input"))
      (node (ref "ST_LINK/V2") (pin "4") (pinfunction "GND_4") (pintype "input"))
      (node (ref "ST_LINK/V2") (pin "5") (pinfunction "TDI_5") (pintype "input"))
      (node (ref "ST_LINK/V2") (pin "6") (pinfunction "GND_6") (pintype "input"))
      (node (ref "ST_LINK/V2") (pin "8") (pinfunction "GND_8") (pintype "input"))
      (node (ref "T1") (pin "15") (pinfunction "15_15") (pintype "passive"))
      (node (ref "T1") (pin "3") (pinfunction "3_3") (pintype "passive"))
      (node (ref "TCA1") (pin "12") (pinfunction "VDD-_12") (pintype "passive"))
      (node (ref "TCA1") (pin "13") (pinfunction "VDD-_13") (pintype "passive"))
      (node (ref "TCA1") (pin "4") (pinfunction "VDD-_4") (pintype "passive"))
      (node (ref "TCA1") (pin "5") (pinfunction "VDD-_5") (pintype "passive"))
      (node (ref "TCA1") (pin "7") (pinfunction "2IN-_7") (pintype "passive"))
      (node (ref "TCA1") (pin "8") (pinfunction "2IN+_8") (pintype "passive"))
      (node (ref "TPS") (pin "11") (pinfunction "GND_11") (pintype "passive"))
      (node (ref "TPS") (pin "3") (pinfunction "PGND_3") (pintype "passive"))
      (node (ref "TPS") (pin "4") (pinfunction "PGND_4") (pintype "passive"))
      (node (ref "TPS") (pin "5") (pinfunction "PGND_5") (pintype "passive"))
      (node (ref "TPS") (pin "8") (pinfunction "SYNC_8") (pintype "passive"))
      (node (ref "UART") (pin "1") (pinfunction "1_1") (pintype "passive"))
    )
    (net (code "39") (name "Net-(AD8-FB)") (class "Default")
      (node (ref "AD8") (pin "7") (pinfunction "FB_7") (pintype "input"))
      (node (ref "R31") (pin "1") (pinfunction "1_1") (pintype "passive"))
      (node (ref "R32") (pin "2") (pinfunction "2_2") (pintype "passive"))
    )
    (net (code "40") (name "Net-(AD8-REF)") (class "Default")
      (node (ref "AD8") (pin "6") (pinfunction "REF_6") (pintype "input"))
      (node (ref "R34") (pin "2") (pinfunction "2_2") (pintype "passive"))
    )
    (net (code "41") (name "Net-(CHG-PadC)") (class "Default")
      (node (ref "CHG") (pin "C") (pinfunction "C_C") (pintype "passive"))
      (node (ref "R1") (pin "1") (pinfunction "1_1") (pintype "passive"))
    )
    (net (code "42") (name "Net-(CONNECT-PadC)") (class "Default")
      (node (ref "CONNECT") (pin "C") (pinfunction "C_C") (pintype "passive"))
      (node (ref "R18") (pin "2") (pinfunction "2_2") (pintype "passive"))
    )
    (net (code "43") (name "Net-(D7-PadA)") (class "Default")
      (node (ref "D7") (pin "A") (pinfunction "A_A") (pintype "passive"))
      (node (ref "R21") (pin "1") (pinfunction "1_1") (pintype "passive"))
    )
    (net (code "44") (name "Net-(D8-PadA)") (class "Default")
      (node (ref "D8") (pin "A") (pinfunction "A_A") (pintype "passive"))
      (node (ref "R22") (pin "1") (pinfunction "1_1") (pintype "passive"))
    )
    (net (code "45") (name "Net-(FULL-PadA)") (class "Default")
      (node (ref "FULL") (pin "A") (pinfunction "A_A") (pintype "passive"))
      (node (ref "R2") (pin "1") (pinfunction "1_1") (pintype "passive"))
    )
    (net (code "46") (name "Net-(L1-Pad2)") (class "Default")
      (node (ref "L1") (pin "2") (pinfunction "2_2") (pintype "passive"))
      (node (ref "TPS") (pin "1") (pinfunction "SW_1") (pintype "passive"))
      (node (ref "TPS") (pin "2") (pinfunction "SW_2") (pintype "passive"))
    )
    (net (code "47") (name "Net-(LM1-C+)") (class "Default")
      (node (ref "C16") (pin "1") (pinfunction "1_1") (pintype "passive"))
      (node (ref "LM1") (pin "5") (pinfunction "C+_5") (pintype "passive"))
    )
    (net (code "48") (name "Net-(LM1-C-)") (class "Default")
      (node (ref "C16") (pin "2") (pinfunction "2_2") (pintype "passive"))
      (node (ref "LM1") (pin "6") (pinfunction "C-_6") (pintype "passive"))
    )
    (net (code "49") (name "Net-(LOW-PadA)") (class "Default")
      (node (ref "LOW") (pin "A") (pinfunction "A_A") (pintype "passive"))
      (node (ref "R6") (pin "1") (pinfunction "1_1") (pintype "passive"))
    )
    (net (code "50") (name "Net-(MCP-PROG)") (class "Default")
      (node (ref "MCP") (pin "5") (pinfunction "PROG_5") (pintype "passive"))
      (node (ref "R3") (pin "1") (pinfunction "1_1") (pintype "passive"))
    )
    (net (code "51") (name "Net-(MCP-STAT)") (class "Default")
      (node (ref "MCP") (pin "1") (pinfunction "STAT_1") (pintype "output"))
      (node (ref "R1") (pin "2") (pinfunction "2_2") (pintype "passive"))
      (node (ref "R2") (pin "2") (pinfunction "2_2") (pintype "passive"))
    )
    (net (code "52") (name "Net-(PWR-PadC)") (class "Default")
      (node (ref "PWR") (pin "C") (pinfunction "C_C") (pintype "passive"))
      (node (ref "R7") (pin "1") (pinfunction "1_1") (pintype "passive"))
    )
    (net (code "53") (name "Net-(Q1-B)") (class "Default")
      (node (ref "Q1") (pin "1") (pinfunction "B_1") (pintype "passive"))
      (node (ref "TPS") (pin "10") (pinfunction "LBO_10") (pintype "passive"))
    )
    (net (code "54") (name "Net-(Q1-C)") (class "Default")
      (node (ref "Q1") (pin "3") (pinfunction "C_3") (pintype "passive"))
      (node (ref "R6") (pin "2") (pinfunction "2_2") (pintype "passive"))
    )
    (net (code "55") (name "Net-(R16-Pad2)") (class "Default")
      (node (ref "R16") (pin "2") (pinfunction "2_2") (pintype "passive"))
      (node (ref "STATE") (pin "C") (pinfunction "C_C") (pintype "passive"))
    )
    (net (code "56") (name "Net-(R23-Pad2)") (class "Default")
      (node (ref "R23") (pin "2") (pinfunction "2_2") (pintype "passive"))
      (node (ref "ST_LINK/V2") (pin "11") (pinfunction "N/C_11") (pintype "input"))
    )
    (net (code "57") (name "Net-(R24-Pad2)") (class "Default")
      (node (ref "R24") (pin "2") (pinfunction "2_2") (pintype "passive"))
      (node (ref "ST_LINK/V2") (pin "17") (pinfunction "N/C_17") (pintype "input"))
    )
    (net (code "58") (name "Net-(R25-Pad2)") (class "Default")
      (node (ref "R25") (pin "2") (pinfunction "2_2") (pintype "passive"))
      (node (ref "ST_LINK/V2") (pin "19") (pinfunction "N/C_19") (pintype "input"))
    )
    (net (code "59") (name "Net-(RN41-PIO2)") (class "Default")
      (node (ref "CONNECT") (pin "A") (pinfunction "A_A") (pintype "passive"))
      (node (ref "RN41") (pin "19") (pinfunction "PIO2_19") (pintype "passive"))
    )
    (net (code "60") (name "Net-(RN41-PIO4)") (class "Default")
      (node (ref "R17") (pin "2") (pinfunction "2_2") (pintype "passive"))
      (node (ref "RN41") (pin "22") (pinfunction "PIO4_22") (pintype "passive"))
    )
    (net (code "61") (name "Net-(RN41-PIO5)") (class "Default")
      (node (ref "RN41") (pin "21") (pinfunction "PIO5_21") (pintype "passive"))
      (node (ref "STATE") (pin "A") (pinfunction "A_A") (pintype "passive"))
    )
    (net (code "62") (name "Net-(STM32F3A-BOOT0)") (class "Default")
      (node (ref "R20") (pin "1") (pinfunction "1_1") (pintype "passive"))
      (node (ref "STM32F3") (pin "60") (pinfunction "BOOT0_60") (pintype "input"))
    )
    (net (code "63") (name "Net-(STM32F3A-PA11)") (class "Default")
      (node (ref "R27") (pin "2") (pinfunction "2_2") (pintype "passive"))
      (node (ref "STM32F3") (pin "44") (pinfunction "PA11_44") (pintype "bidirectional"))
    )
    (net (code "64") (name "Net-(STM32F3A-PA12)") (class "Default")
      (node (ref "R28") (pin "2") (pinfunction "2_2") (pintype "passive"))
      (node (ref "STM32F3") (pin "45") (pinfunction "PA12_45") (pintype "bidirectional"))
    )
    (net (code "65") (name "Net-(STM32F3A-PC8)") (class "Default")
      (node (ref "R21") (pin "2") (pinfunction "2_2") (pintype "passive"))
      (node (ref "STM32F3") (pin "39") (pinfunction "PC8_39") (pintype "bidirectional"))
    )
    (net (code "66") (name "Net-(STM32F3A-PC9)") (class "Default")
      (node (ref "R22") (pin "2") (pinfunction "2_2") (pintype "passive"))
      (node (ref "STM32F3") (pin "40") (pinfunction "PC9_40") (pintype "bidirectional"))
    )
    (net (code "67") (name "Net-(STM32F3A-PF0-OSC_IN(PF0))") (class "Default")
      (node (ref "C23") (pin "1") (pinfunction "1_1") (pintype "passive"))
      (node (ref "STM32F3") (pin "5") (pinfunction "PF0-OSC_IN(PF0)_5") (pintype "bidirectional"))
      (node (ref "X1") (pin "1") (pinfunction "OSC1_1") (pintype "passive"))
    )
    (net (code "68") (name "Net-(STM32F3A-PF1-OSC_OUT(PF1))") (class "Default")
      (node (ref "R19") (pin "2") (pinfunction "2_2") (pintype "passive"))
      (node (ref "STM32F3") (pin "6") (pinfunction "PF1-OSC_OUT(PF1)_6") (pintype "bidirectional"))
    )
    (net (code "69") (name "Net-(TLC1-4IN-)") (class "Default")
      (node (ref "R14") (pin "2") (pinfunction "2_2") (pintype "passive"))
      (node (ref "R15") (pin "1") (pinfunction "1_1") (pintype "passive"))
      (node (ref "TLC1") (pin "13") (pinfunction "4IN-_13") (pintype "passive"))
    )
    (net (code "70") (name "Net-(TPS-LBI)") (class "Default")
      (node (ref "R4") (pin "1") (pinfunction "1_1") (pintype "passive"))
      (node (ref "R5") (pin "1") (pinfunction "1_1") (pintype "passive"))
      (node (ref "TPS") (pin "7") (pinfunction "LBI_7") (pintype "passive"))
    )
    (net (code "71") (name "Net-(X1-OSC2)") (class "Default")
      (node (ref "C24") (pin "1") (pinfunction "1_1") (pintype "passive"))
      (node (ref "R19") (pin "1") (pinfunction "1_1") (pintype "passive"))
      (node (ref "X1") (pin "2") (pinfunction "OSC2_2") (pintype "passive"))
    )
    (net (code "72") (name "unconnected-(DS7-OS-Pad3)") (class "Default")
      (node (ref "DS7") (pin "3") (pinfunction "OS_3") (pintype "output"))
    )
    (net (code "73") (name "unconnected-(JSTPH-PadMP1)") (class "Default")
      (node (ref "JSTPH") (pin "MP1") (pinfunction "MP1_MP1") (pintype "passive"))
    )
    (net (code "74") (name "unconnected-(JSTPH-PadMP2)") (class "Default")
      (node (ref "JSTPH") (pin "MP2") (pinfunction "MP2_MP2") (pintype "passive"))
    )
    (net (code "75") (name "unconnected-(LM2-VOUT-Pad2)") (class "Default")
      (node (ref "LM2") (pin "2") (pinfunction "VOUT_2") (pintype "passive"))
    )
    (net (code "76") (name "unconnected-(MicroUSB-ID-Pad4)") (class "Default")
      (node (ref "MicroUSB") (pin "4") (pinfunction "ID_4") (pintype "passive"))
    )
    (net (code "77") (name "unconnected-(MicroUSB-SHLD-Pad6)") (class "Default")
      (node (ref "MicroUSB") (pin "6") (pinfunction "SHLD_6") (pintype "passive"))
    )
    (net (code "78") (name "unconnected-(MicroUSB-SHLD-Pad7)") (class "Default")
      (node (ref "MicroUSB") (pin "7") (pinfunction "SHLD_7") (pintype "passive"))
    )
    (net (code "79") (name "unconnected-(MicroUSB-SHLD-Pad8)") (class "Default")
      (node (ref "MicroUSB") (pin "8") (pinfunction "SHLD_8") (pintype "passive"))
    )
    (net (code "80") (name "unconnected-(MicroUSB-SHLD-Pad9)") (class "Default")
      (node (ref "MicroUSB") (pin "9") (pinfunction "SHLD_9") (pintype "passive"))
    )
    (net (code "81") (name "unconnected-(MicroUSB-SHLD-Pad10)") (class "Default")
      (node (ref "MicroUSB") (pin "10") (pinfunction "SHLD_10") (pintype "passive"))
    )
    (net (code "82") (name "unconnected-(MicroUSB-SHLD-Pad11)") (class "Default")
      (node (ref "MicroUSB") (pin "11") (pinfunction "SHLD_11") (pintype "passive"))
    )
    (net (code "83") (name "unconnected-(RESET-Pad2)") (class "Default")
      (node (ref "RESET") (pin "2") (pinfunction "2_2") (pintype "passive"))
    )
    (net (code "84") (name "unconnected-(RESET-Pad4)") (class "Default")
      (node (ref "RESET") (pin "4") (pinfunction "4_4") (pintype "passive"))
    )
    (net (code "85") (name "unconnected-(RN41-AIO0-Pad30)") (class "Default")
      (node (ref "RN41") (pin "30") (pinfunction "AIO0_30") (pintype "passive"))
    )
    (net (code "86") (name "unconnected-(RN41-AIO1-Pad35)") (class "Default")
      (node (ref "RN41") (pin "35") (pinfunction "AIO1_35") (pintype "passive"))
    )
    (net (code "87") (name "unconnected-(RN41-PCMCLK-Pad7)") (class "Default")
      (node (ref "RN41") (pin "7") (pinfunction "PCMCLK_7") (pintype "passive"))
    )
    (net (code "88") (name "unconnected-(RN41-PCMIN-Pad9)") (class "Default")
      (node (ref "RN41") (pin "9") (pinfunction "PCMIN_9") (pintype "passive"))
    )
    (net (code "89") (name "unconnected-(RN41-PCMOUT-Pad10)") (class "Default")
      (node (ref "RN41") (pin "10") (pinfunction "PCMOUT_10") (pintype "passive"))
    )
    (net (code "90") (name "unconnected-(RN41-PCMSYNC-Pad8)") (class "Default")
      (node (ref "RN41") (pin "8") (pinfunction "PCMSYNC_8") (pintype "passive"))
    )
    (net (code "91") (name "unconnected-(RN41-PIO3-Pad20)") (class "Default")
      (node (ref "RN41") (pin "20") (pinfunction "PIO3_20") (pintype "passive"))
    )
    (net (code "92") (name "unconnected-(RN41-PIO6-Pad3)") (class "Default")
      (node (ref "RN41") (pin "3") (pinfunction "PIO6_3") (pintype "passive"))
    )
    (net (code "93") (name "unconnected-(RN41-PIO7-Pad4)") (class "Default")
      (node (ref "RN41") (pin "4") (pinfunction "PIO7_4") (pintype "passive"))
    )
    (net (code "94") (name "unconnected-(RN41-PIO8-Pad31)") (class "Default")
      (node (ref "RN41") (pin "31") (pinfunction "PIO8_31") (pintype "passive"))
    )
    (net (code "95") (name "unconnected-(RN41-PIO9-Pad32)") (class "Default")
      (node (ref "RN41") (pin "32") (pinfunction "PIO9_32") (pintype "passive"))
    )
    (net (code "96") (name "unconnected-(RN41-PIO10-Pad33)") (class "Default")
      (node (ref "RN41") (pin "33") (pinfunction "PIO10_33") (pintype "passive"))
    )
    (net (code "97") (name "unconnected-(RN41-PIO11-Pad34)") (class "Default")
      (node (ref "RN41") (pin "34") (pinfunction "PIO11_34") (pintype "passive"))
    )
    (net (code "98") (name "unconnected-(RN41-RESET-Pad5)") (class "Default")
      (node (ref "RN41") (pin "5") (pinfunction "RESET_5") (pintype "passive"))
    )
    (net (code "99") (name "unconnected-(RN41-SPICLK-Pad6)") (class "Default")
      (node (ref "RN41") (pin "6") (pinfunction "SPICLK_6") (pintype "passive"))
    )
    (net (code "100") (name "unconnected-(RN41-SPICSB-Pad23)") (class "Default")
      (node (ref "RN41") (pin "23") (pinfunction "SPICSB_23") (pintype "passive"))
    )
    (net (code "101") (name "unconnected-(RN41-SPIMISO-Pad24)") (class "Default")
      (node (ref "RN41") (pin "24") (pinfunction "SPIMISO_24") (pintype "passive"))
    )
    (net (code "102") (name "unconnected-(RN41-SPIMOSI-Pad2)") (class "Default")
      (node (ref "RN41") (pin "2") (pinfunction "SPIMOSI_2") (pintype "passive"))
    )
    (net (code "103") (name "unconnected-(RN41-UARTCTS-Pad16)") (class "Default")
      (node (ref "RN41") (pin "16") (pinfunction "UARTCTS_16") (pintype "passive"))
    )
    (net (code "104") (name "unconnected-(RN41-UARTRTS-Pad15)") (class "Default")
      (node (ref "RN41") (pin "15") (pinfunction "UARTRTS_15") (pintype "passive"))
    )
    (net (code "105") (name "unconnected-(RN41-USBD+-Pad17)") (class "Default")
      (node (ref "RN41") (pin "17") (pinfunction "USBD+_17") (pintype "passive"))
    )
    (net (code "106") (name "unconnected-(RN41-USBD--Pad18)") (class "Default")
      (node (ref "RN41") (pin "18") (pinfunction "USBD-_18") (pintype "passive"))
    )
    (net (code "107") (name "unconnected-(STM32F3A-PA1-Pad15)") (class "Default")
      (node (ref "STM32F3") (pin "15") (pinfunction "PA1_15") (pintype "bidirectional"))
    )
    (net (code "108") (name "unconnected-(STM32F3A-PA6-Pad22)") (class "Default")
      (node (ref "STM32F3") (pin "22") (pinfunction "PA6_22") (pintype "bidirectional"))
    )
    (net (code "109") (name "unconnected-(STM32F3A-PA7-Pad23)") (class "Default")
      (node (ref "STM32F3") (pin "23") (pinfunction "PA7_23") (pintype "bidirectional"))
    )
    (net (code "110") (name "unconnected-(STM32F3A-PA9-Pad42)") (class "Default")
      (node (ref "STM32F3") (pin "42") (pinfunction "PA9_42") (pintype "bidirectional"))
    )
    (net (code "111") (name "unconnected-(STM32F3A-PA10-Pad43)") (class "Default")
      (node (ref "STM32F3") (pin "43") (pinfunction "PA10_43") (pintype "bidirectional"))
    )
    (net (code "112") (name "unconnected-(STM32F3A-PA15-Pad50)") (class "Default")
      (node (ref "STM32F3") (pin "50") (pinfunction "PA15_50") (pintype "bidirectional"))
    )
    (net (code "113") (name "unconnected-(STM32F3A-PB0-Pad26)") (class "Default")
      (node (ref "STM32F3") (pin "26") (pinfunction "PB0_26") (pintype "bidirectional"))
    )
    (net (code "114") (name "unconnected-(STM32F3A-PB1-Pad27)") (class "Default")
      (node (ref "STM32F3") (pin "27") (pinfunction "PB1_27") (pintype "bidirectional"))
    )
    (net (code "115") (name "unconnected-(STM32F3A-PB2-Pad28)") (class "Default")
      (node (ref "STM32F3") (pin "28") (pinfunction "PB2_28") (pintype "bidirectional"))
    )
    (net (code "116") (name "unconnected-(STM32F3A-PB3-Pad55)") (class "Default")
      (node (ref "STM32F3") (pin "55") (pinfunction "PB3_55") (pintype "bidirectional"))
    )
    (net (code "117") (name "unconnected-(STM32F3A-PB4-Pad56)") (class "Default")
      (node (ref "STM32F3") (pin "56") (pinfunction "PB4_56") (pintype "bidirectional"))
    )
    (net (code "118") (name "unconnected-(STM32F3A-PB5-Pad57)") (class "Default")
      (node (ref "STM32F3") (pin "57") (pinfunction "PB5_57") (pintype "bidirectional"))
    )
    (net (code "119") (name "unconnected-(STM32F3A-PB10-Pad29)") (class "Default")
      (node (ref "STM32F3") (pin "29") (pinfunction "PB10_29") (pintype "bidirectional"))
    )
    (net (code "120") (name "unconnected-(STM32F3A-PB11-Pad30)") (class "Default")
      (node (ref "STM32F3") (pin "30") (pinfunction "PB11_30") (pintype "bidirectional"))
    )
    (net (code "121") (name "unconnected-(STM32F3A-PC0-Pad8)") (class "Default")
      (node (ref "STM32F3") (pin "8") (pinfunction "PC0_8") (pintype "bidirectional"))
    )
    (net (code "122") (name "unconnected-(STM32F3A-PC1-Pad9)") (class "Default")
      (node (ref "STM32F3") (pin "9") (pinfunction "PC1_9") (pintype "bidirectional"))
    )
    (net (code "123") (name "unconnected-(STM32F3A-PC2-Pad10)") (class "Default")
      (node (ref "STM32F3") (pin "10") (pinfunction "PC2_10") (pintype "bidirectional"))
    )
    (net (code "124") (name "unconnected-(STM32F3A-PC3-Pad11)") (class "Default")
      (node (ref "STM32F3") (pin "11") (pinfunction "PC3_11") (pintype "bidirectional"))
    )
    (net (code "125") (name "unconnected-(STM32F3A-PC4-Pad24)") (class "Default")
      (node (ref "STM32F3") (pin "24") (pinfunction "PC4_24") (pintype "bidirectional"))
    )
    (net (code "126") (name "unconnected-(STM32F3A-PC5-Pad25)") (class "Default")
      (node (ref "STM32F3") (pin "25") (pinfunction "PC5_25") (pintype "bidirectional"))
    )
    (net (code "127") (name "unconnected-(STM32F3A-PC6-Pad37)") (class "Default")
      (node (ref "STM32F3") (pin "37") (pinfunction "PC6_37") (pintype "bidirectional"))
    )
    (net (code "128") (name "unconnected-(STM32F3A-PC7-Pad38)") (class "Default")
      (node (ref "STM32F3") (pin "38") (pinfunction "PC7_38") (pintype "bidirectional"))
    )
    (net (code "129") (name "unconnected-(STM32F3A-PC12-Pad53)") (class "Default")
      (node (ref "STM32F3") (pin "53") (pinfunction "PC12_53") (pintype "bidirectional"))
    )
    (net (code "130") (name "unconnected-(STM32F3A-PC13-Pad2)") (class "Default")
      (node (ref "STM32F3") (pin "2") (pinfunction "PC13_2") (pintype "bidirectional"))
    )
    (net (code "131") (name "unconnected-(STM32F3A-PC14-OSC32_IN(PC14)-Pad3)") (class "Default")
      (node (ref "STM32F3") (pin "3") (pinfunction "PC14-OSC32_IN(PC14)_3") (pintype "bidirectional"))
    )
    (net (code "132") (name "unconnected-(STM32F3A-PC15-OSC32_OUT(PC15)-Pad4)") (class "Default")
      (node (ref "STM32F3") (pin "4") (pinfunction "PC15-OSC32_OUT(PC15)_4") (pintype "bidirectional"))
    )
    (net (code "133") (name "unconnected-(STM32F3A-PD2-Pad54)") (class "Default")
      (node (ref "STM32F3") (pin "54") (pinfunction "PD2_54") (pintype "bidirectional"))
    )
    (net (code "134") (name "unconnected-(SW-PWR-Pad1)") (class "Default")
      (node (ref "SW-PWR") (pin "1") (pinfunction "1_1") (pintype "passive"))
    )
    (net (code "135") (name "unconnected-(T1-Pad2)") (class "Default")
      (node (ref "T1") (pin "2") (pinfunction "2_2") (pintype "passive"))
    )
    (net (code "136") (name "unconnected-(T1-Pad4)") (class "Default")
      (node (ref "T1") (pin "4") (pinfunction "4_4") (pintype "passive"))
    )
    (net (code "137") (name "unconnected-(T1-Pad5)") (class "Default")
      (node (ref "T1") (pin "5") (pinfunction "5_5") (pintype "passive"))
    )
    (net (code "138") (name "unconnected-(T1-Pad6)") (class "Default")
      (node (ref "T1") (pin "6") (pinfunction "6_6") (pintype "passive"))
    )
    (net (code "139") (name "unconnected-(T1-Pad8)") (class "Default")
      (node (ref "T1") (pin "8") (pinfunction "8_8") (pintype "passive"))
    )
    (net (code "140") (name "unconnected-(T1-Pad10)") (class "Default")
      (node (ref "T1") (pin "10") (pinfunction "10_10") (pintype "passive"))
    )
    (net (code "141") (name "unconnected-(T1-Pad11)") (class "Default")
      (node (ref "T1") (pin "11") (pinfunction "11_11") (pintype "passive"))
    )
    (net (code "142") (name "unconnected-(T1-Pad12)") (class "Default")
      (node (ref "T1") (pin "12") (pinfunction "12_12") (pintype "passive"))
    )
    (net (code "143") (name "unconnected-(T1-Pad14)") (class "Default")
      (node (ref "T1") (pin "14") (pinfunction "14_14") (pintype "passive"))
    )
    (net (code "144") (name "unconnected-(T1-Pad16)") (class "Default")
      (node (ref "T1") (pin "16") (pinfunction "16_16") (pintype "passive"))
    )
    (net (code "145") (name "unconnected-(T1-Pad18)") (class "Default")
      (node (ref "T1") (pin "18") (pinfunction "18_18") (pintype "passive"))
    )
    (net (code "146") (name "unconnected-(T1-Pad19)") (class "Default")
      (node (ref "T1") (pin "19") (pinfunction "19_19") (pintype "passive"))
    )
    (net (code "147") (name "unconnected-(T1-Pad20)") (class "Default")
      (node (ref "T1") (pin "20") (pinfunction "20_20") (pintype "passive"))
    )
    (net (code "148") (name "unconnected-(T1-Pad22)") (class "Default")
      (node (ref "T1") (pin "22") (pinfunction "22_22") (pintype "passive"))
    )
    (net (code "149") (name "unconnected-(T1-Pad23)") (class "Default")
      (node (ref "T1") (pin "23") (pinfunction "23_23") (pintype "passive"))
    )
    (net (code "150") (name "unconnected-(T1-Pad24)") (class "Default")
      (node (ref "T1") (pin "24") (pinfunction "24_24") (pintype "passive"))
    )
    (net (code "151") (name "unconnected-(T1-Pad26)") (class "Default")
      (node (ref "T1") (pin "26") (pinfunction "26_26") (pintype "passive"))
    )
    (net (code "152") (name "unconnected-(T1-Pad27)") (class "Default")
      (node (ref "T1") (pin "27") (pinfunction "27_27") (pintype "passive"))
    )
    (net (code "153") (name "unconnected-(T1-Pad28)") (class "Default")
      (node (ref "T1") (pin "28") (pinfunction "28_28") (pintype "passive"))
    )
    (net (code "154") (name "unconnected-(T1-Pad30)") (class "Default")
      (node (ref "T1") (pin "30") (pinfunction "30_30") (pintype "passive"))
    )
    (net (code "155") (name "unconnected-(T1-Pad31)") (class "Default")
      (node (ref "T1") (pin "31") (pinfunction "31_31") (pintype "passive"))
    )
    (net (code "156") (name "unconnected-(T1-Pad32)") (class "Default")
      (node (ref "T1") (pin "32") (pinfunction "32_32") (pintype "passive"))
    )
    (net (code "157") (name "unconnected-(T1-Pad34)") (class "Default")
      (node (ref "T1") (pin "34") (pinfunction "34_34") (pintype "passive"))
    )
    (net (code "158") (name "unconnected-(T1-Pad35)") (class "Default")
      (node (ref "T1") (pin "35") (pinfunction "35_35") (pintype "passive"))
    )
    (net (code "159") (name "unconnected-(T1-Pad36)") (class "Default")
      (node (ref "T1") (pin "36") (pinfunction "36_36") (pintype "passive"))
    )
    (net (code "160") (name "unconnected-(T1-Pad38)") (class "Default")
      (node (ref "T1") (pin "38") (pinfunction "38_38") (pintype "passive"))
    )
    (net (code "161") (name "unconnected-(T1-Pad39)") (class "Default")
      (node (ref "T1") (pin "39") (pinfunction "39_39") (pintype "passive"))
    )
    (net (code "162") (name "unconnected-(T1-Pad40)") (class "Default")
      (node (ref "T1") (pin "40") (pinfunction "40_40") (pintype "passive"))
    )
    (net (code "163") (name "unconnected-(T1-Pad42)") (class "Default")
      (node (ref "T1") (pin "42") (pinfunction "42_42") (pintype "passive"))
    )
    (net (code "164") (name "unconnected-(T1-Pad43)") (class "Default")
      (node (ref "T1") (pin "43") (pinfunction "43_43") (pintype "passive"))
    )
    (net (code "165") (name "unconnected-(T1-Pad44)") (class "Default")
      (node (ref "T1") (pin "44") (pinfunction "44_44") (pintype "passive"))
    )
    (net (code "166") (name "unconnected-(T1-Pad46)") (class "Default")
      (node (ref "T1") (pin "46") (pinfunction "46_46") (pintype "passive"))
    )
    (net (code "167") (name "unconnected-(T1-Pad47)") (class "Default")
      (node (ref "T1") (pin "47") (pinfunction "47_47") (pintype "passive"))
    )
    (net (code "168") (name "unconnected-(T1-Pad48)") (class "Default")
      (node (ref "T1") (pin "48") (pinfunction "48_48") (pintype "passive"))
    )
    (net (code "169") (name "unconnected-(T1-Pad50)") (class "Default")
      (node (ref "T1") (pin "50") (pinfunction "50_50") (pintype "passive"))
    )
    (net (code "170") (name "unconnected-(T1-Pad52)") (class "Default")
      (node (ref "T1") (pin "52") (pinfunction "52_52") (pintype "passive"))
    )
    (net (code "171") (name "unconnected-(T1-PadMP1)") (class "Default")
      (node (ref "T1") (pin "MP1") (pinfunction "MP1_MP1") (pintype "passive"))
    )
    (net (code "172") (name "unconnected-(T1-PadMP2)") (class "Default")
      (node (ref "T1") (pin "MP2") (pinfunction "MP2_MP2") (pintype "passive"))
    )
    (net (code "173") (name "unconnected-(T2-PadMP1L)") (class "Default")
      (node (ref "T2") (pin "MP1L") (pinfunction "MP1L_MP1L") (pintype "passive"))
    )
    (net (code "174") (name "unconnected-(T2-PadMP2L)") (class "Default")
      (node (ref "T2") (pin "MP2L") (pinfunction "MP2L_MP2L") (pintype "passive"))
    )
    (net (code "175") (name "unconnected-(T2-PadMP3L)") (class "Default")
      (node (ref "T2") (pin "MP3L") (pinfunction "MP3L_MP3L") (pintype "passive"))
    )
    (net (code "176") (name "unconnected-(T2-PadMP4L)") (class "Default")
      (node (ref "T2") (pin "MP4L") (pinfunction "MP4L_MP4L") (pintype "passive"))
    )
    (net (code "177") (name "unconnected-(TCA1-2OUT-Pad2)") (class "Default")
      (node (ref "TCA1") (pin "2") (pinfunction "2OUT_2") (pintype "passive"))
    )
    (net (code "178") (name "unconnected-(TCA1-NC-Pad3)") (class "Default")
      (node (ref "TCA1") (pin "3") (pinfunction "NC_3") (pintype "passive"))
    )
    (net (code "179") (name "unconnected-(TCA1-NC-Pad6)") (class "Default")
      (node (ref "TCA1") (pin "6") (pinfunction "NC_6") (pintype "passive"))
    )
    (net (code "180") (name "unconnected-(TCA1-NC-Pad11)") (class "Default")
      (node (ref "TCA1") (pin "11") (pinfunction "NC_11") (pintype "passive"))
    )
    (net (code "181") (name "unconnected-(TCA1-NC-Pad14)") (class "Default")
      (node (ref "TCA1") (pin "14") (pinfunction "NC_14") (pintype "passive"))
    )
    (net (code "182") (name "unconnected-(TCA1-NC-Pad15)") (class "Default")
      (node (ref "TCA1") (pin "15") (pinfunction "NC_15") (pintype "passive"))
    )
    (net (code "183") (name "unconnected-(TPS-FB-Pad12)") (class "Default")
      (node (ref "TPS") (pin "12") (pinfunction "FB_12") (pintype "passive"))
    )
    (net (code "184") (name "unconnected-(TPS-NC-Pad16)") (class "Default")
      (node (ref "TPS") (pin "16") (pinfunction "NC_16") (pintype "passive"))
    )
    (net (code "185") (name "unconnected-(UART-Pad2)") (class "Default")
      (node (ref "UART") (pin "2") (pinfunction "2_2") (pintype "passive"))
    )
    (net (code "186") (name "unconnected-(UART-Pad6)") (class "Default")
      (node (ref "UART") (pin "6") (pinfunction "6_6") (pintype "passive"))
    )
  )
)
